# Controller_Board_Main.net
KiCad netlist of a schematic drawn in Altium Designer
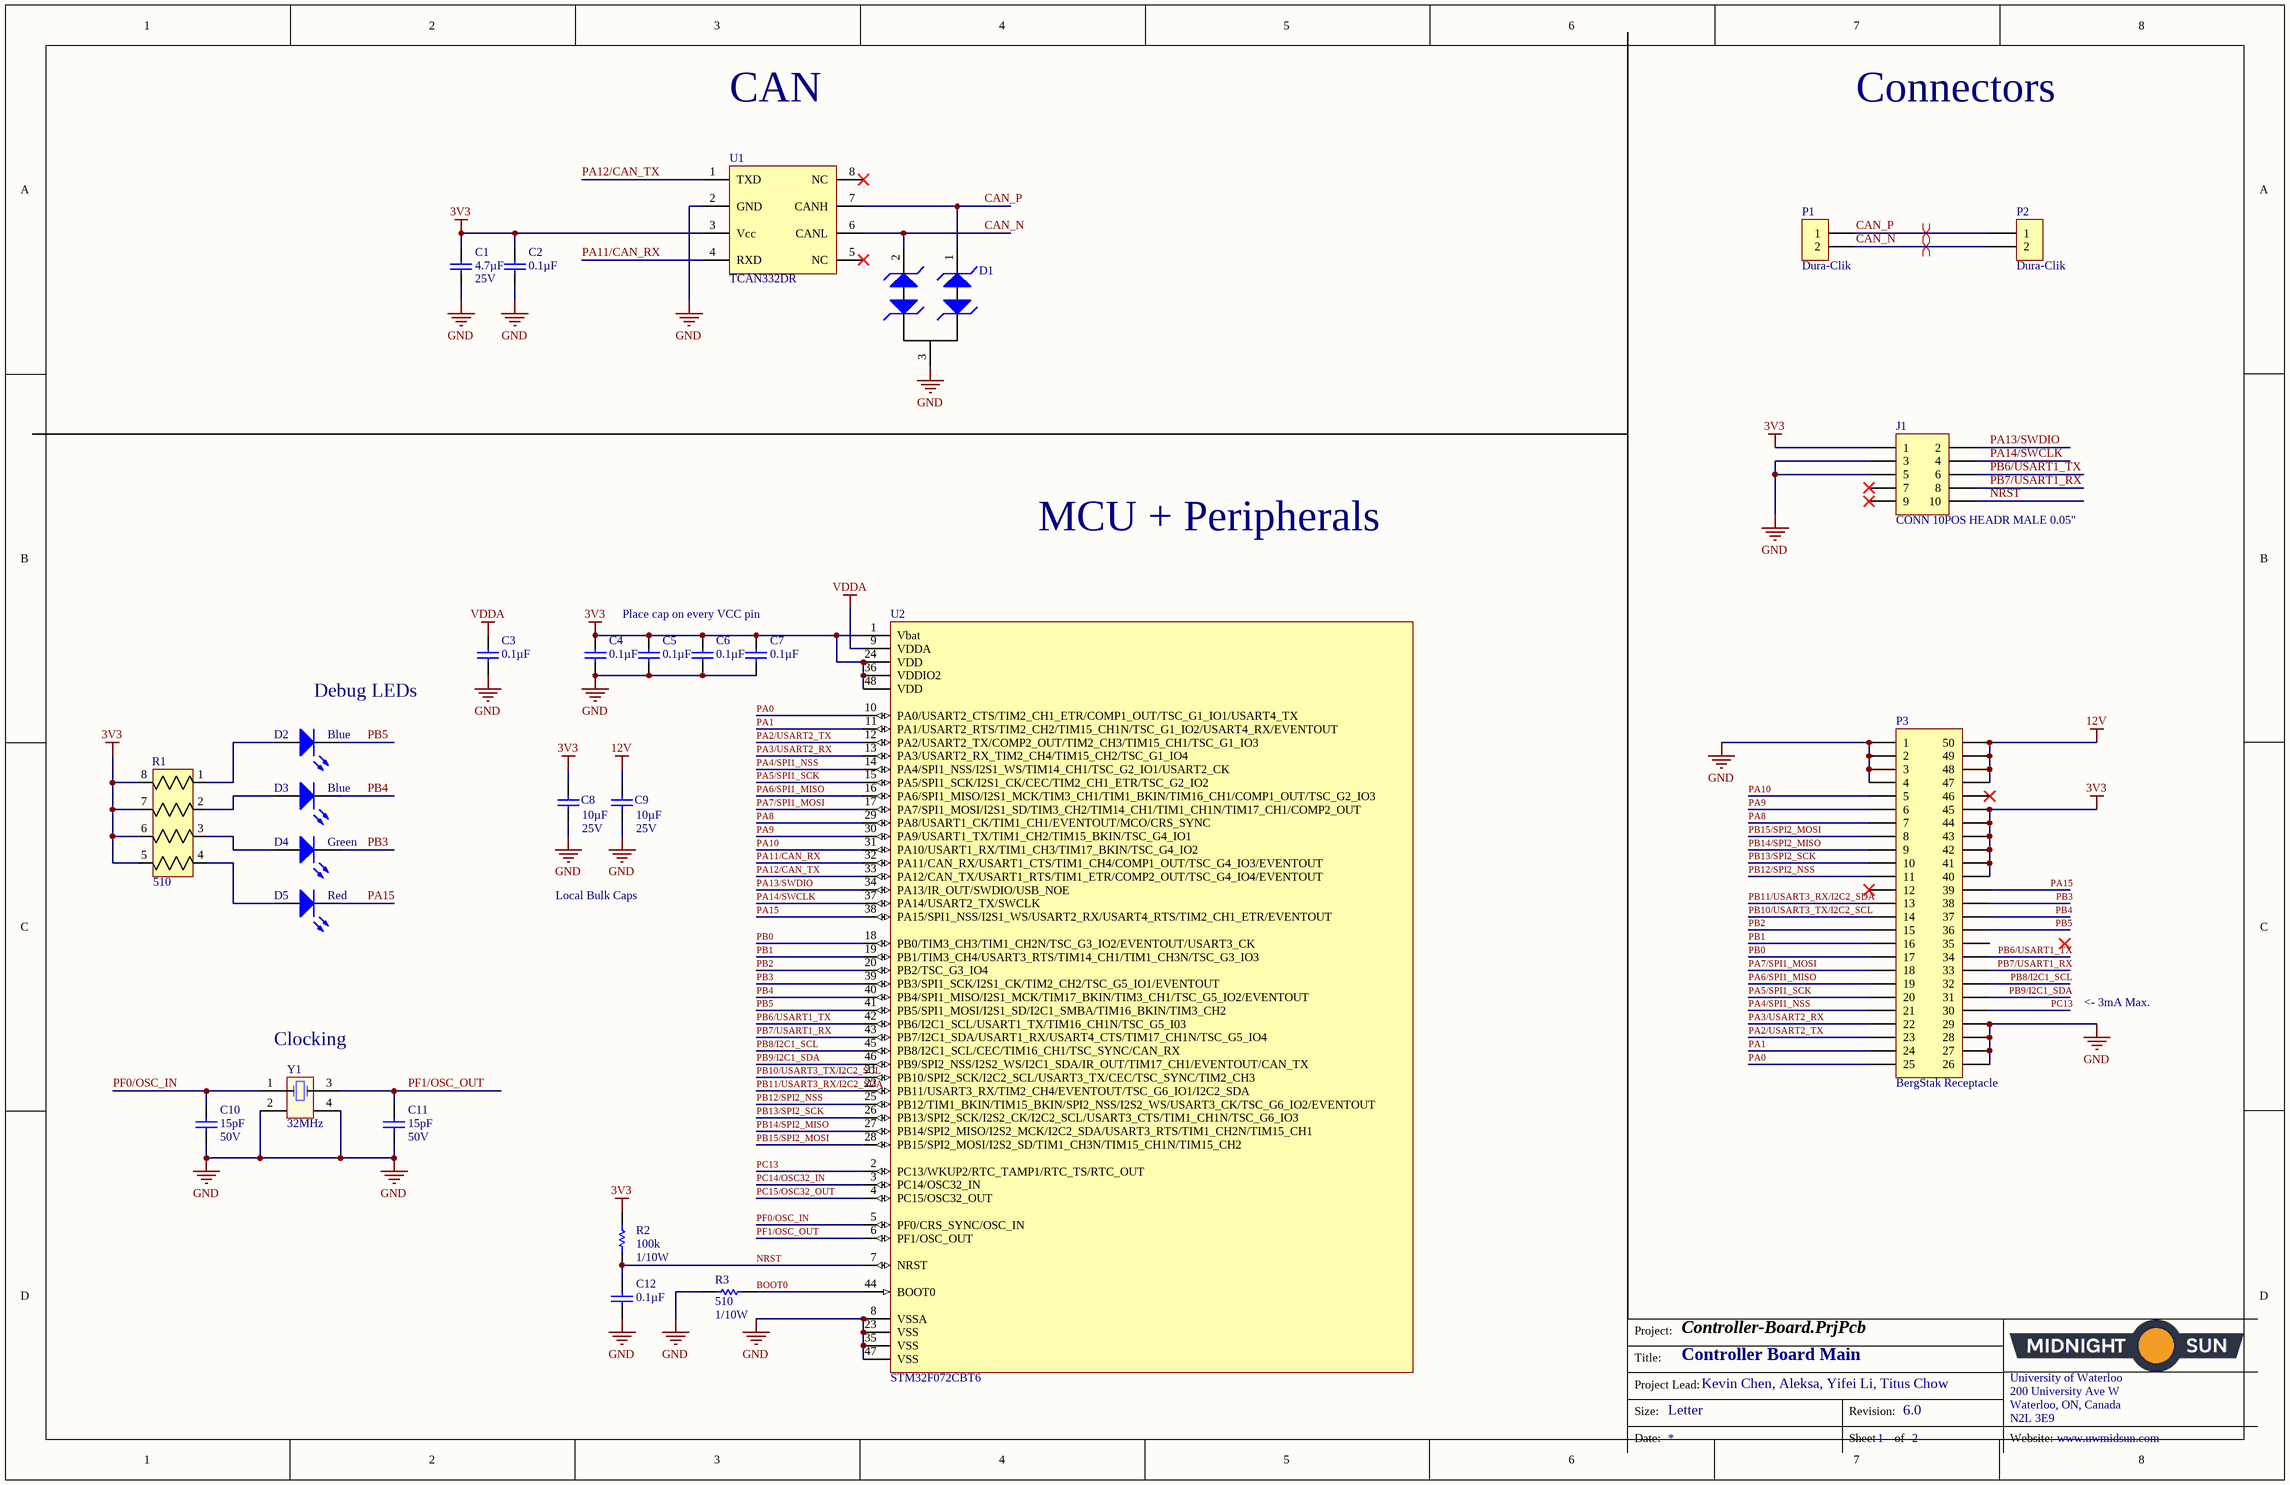
[diagram p0: Controller_Board_Main.SchDoc]

(export (version "E")
  (design (tool "Eeschema 10.0.6"))
  (components
    (comp (ref "C1")
      (value "CAP CER 4.7UF 25V 10% X5R 0603")
      (footprint "CAP, 0603")
      (description "4.7µF ±10% 25V Ceramic Capacitor X5R 0603 (1608 Metric)")
      (fields
        (field (name "VOLTAGE") "25V")
        (field (name "TOLERANCE") "±10%")
        (field (name "CAPACITANCE") "4.7µF")
      )
      (libsource (lib "Schematic Diagrams") (part "CAP CER 4.7UF 25V 10% X5R 0603"))
    )
    (comp (ref "C2")
      (value "CAP CER 0.1UF 50V 10% X7R 0603")
      (footprint "CAP, 0603")
      (description "0.10µF ±10% 50V Ceramic Capacitor X7R 0603 (1608 Metric)")
      (fields
        (field (name "VOLTAGE") "50V")
        (field (name "TOLERANCE") "±10%")
        (field (name "CAPACITANCE") "0.1µF")
      )
      (libsource (lib "Schematic Diagrams") (part "CAP CER 0.1UF 50V 10% X7R 0603"))
    )
    (comp (ref "C3")
      (value "CAP CER 0.1UF 50V 10% X7R 0603")
      (footprint "CAP, 0603")
      (description "0.10µF ±10% 50V Ceramic Capacitor X7R 0603 (1608 Metric)")
      (fields
        (field (name "VOLTAGE") "50V")
        (field (name "TOLERANCE") "±10%")
        (field (name "CAPACITANCE") "0.1µF")
      )
      (libsource (lib "Schematic Diagrams") (part "CAP CER 0.1UF 50V 10% X7R 0603"))
    )
    (comp (ref "C4")
      (value "CAP CER 0.1UF 50V 10% X7R 0603")
      (footprint "CAP, 0603")
      (description "0.10µF ±10% 50V Ceramic Capacitor X7R 0603 (1608 Metric)")
      (fields
        (field (name "VOLTAGE") "50V")
        (field (name "TOLERANCE") "±10%")
        (field (name "CAPACITANCE") "0.1µF")
      )
      (libsource (lib "Schematic Diagrams") (part "CAP CER 0.1UF 50V 10% X7R 0603"))
    )
    (comp (ref "C5")
      (value "CAP CER 0.1UF 50V 10% X7R 0603")
      (footprint "CAP, 0603")
      (description "0.10µF ±10% 50V Ceramic Capacitor X7R 0603 (1608 Metric)")
      (fields
        (field (name "VOLTAGE") "50V")
        (field (name "TOLERANCE") "±10%")
        (field (name "CAPACITANCE") "0.1µF")
      )
      (libsource (lib "Schematic Diagrams") (part "CAP CER 0.1UF 50V 10% X7R 0603"))
    )
    (comp (ref "C6")
      (value "CAP CER 0.1UF 50V 10% X7R 0603")
      (footprint "CAP, 0603")
      (description "0.10µF ±10% 50V Ceramic Capacitor X7R 0603 (1608 Metric)")
      (fields
        (field (name "VOLTAGE") "50V")
        (field (name "TOLERANCE") "±10%")
        (field (name "CAPACITANCE") "0.1µF")
      )
      (libsource (lib "Schematic Diagrams") (part "CAP CER 0.1UF 50V 10% X7R 0603"))
    )
    (comp (ref "C7")
      (value "CAP CER 0.1UF 50V 10% X7R 0603")
      (footprint "CAP, 0603")
      (description "0.10µF ±10% 50V Ceramic Capacitor X7R 0603 (1608 Metric)")
      (fields
        (field (name "VOLTAGE") "50V")
        (field (name "TOLERANCE") "±10%")
        (field (name "CAPACITANCE") "0.1µF")
      )
      (libsource (lib "Schematic Diagrams") (part "CAP CER 0.1UF 50V 10% X7R 0603"))
    )
    (comp (ref "C8")
      (value "CAP CER 10uF 25V 10% X5R 0805")
      (footprint "CAP, 0805")
      (description "10µF ±10% 25V Ceramic Capacitor X5R 0805 (2012 Metric)")
      (fields
        (field (name "MANUFACTURER") "Murata Electronics North America")
        (field (name "MANUFACTURER PART NUMBER") "GRM21BR61E106KA73L")
        (field (name "VOLTAGE - RATED") "25V")
        (field (name "CAPACITANCE") "10µF")
      )
      (libsource (lib "Schematic Diagrams") (part "CAP CER 10uF 25V 10% X5R 0805"))
    )
    (comp (ref "C9")
      (value "CAP CER 10uF 25V 10% X5R 0805")
      (footprint "CAP, 0805")
      (description "10µF ±10% 25V Ceramic Capacitor X5R 0805 (2012 Metric)")
      (fields
        (field (name "MANUFACTURER") "Murata Electronics North America")
        (field (name "MANUFACTURER PART NUMBER") "GRM21BR61E106KA73L")
        (field (name "VOLTAGE - RATED") "25V")
        (field (name "CAPACITANCE") "10µF")
      )
      (libsource (lib "Schematic Diagrams") (part "CAP CER 10uF 25V 10% X5R 0805"))
    )
    (comp (ref "C10")
      (value "CAP CER 15PF 50V ±5% NPO 0603")
      (footprint "CAP, 0603")
      (description "15pF ±5% 50V Ceramic Capacitor C0G, NP0 0603 (1608 Metric)")
      (fields
        (field (name "VOLTAGE") "50V")
        (field (name "TOLERANCE") "±5%")
        (field (name "CAPACITANCE") "15pF")
      )
      (libsource (lib "Schematic Diagrams") (part "CAP CER 15PF 50V ±5% NPO 0603"))
    )
    (comp (ref "C11")
      (value "CAP CER 15PF 50V ±5% NPO 0603")
      (footprint "CAP, 0603")
      (description "15pF ±5% 50V Ceramic Capacitor C0G, NP0 0603 (1608 Metric)")
      (fields
        (field (name "VOLTAGE") "50V")
        (field (name "TOLERANCE") "±5%")
        (field (name "CAPACITANCE") "15pF")
      )
      (libsource (lib "Schematic Diagrams") (part "CAP CER 15PF 50V ±5% NPO 0603"))
    )
    (comp (ref "C12")
      (value "CAP CER 0.1UF 50V 10% X7R 0603")
      (footprint "CAP, 0603")
      (description "0.10µF ±10% 50V Ceramic Capacitor X7R 0603 (1608 Metric)")
      (fields
        (field (name "VOLTAGE") "50V")
        (field (name "TOLERANCE") "±10%")
        (field (name "CAPACITANCE") "0.1µF")
      )
      (libsource (lib "Schematic Diagrams") (part "CAP CER 0.1UF 50V 10% X7R 0603"))
    )
    (comp (ref "D1")
      (value "DIODE TVS 24VWM 70VC SOT23")
      (footprint "SOT23")
      (description "TVS DIODE 24VWM 70VC SOT23")
      (libsource (lib "Schematic Diagrams") (part "DIODE TVS 24VWM 70VC SOT23"))
    )
    (comp (ref "D2")
      (value "LED BLUE CLEAR 2.8V 0603")
      (footprint "DIOC1608X06N")
      (description "Blue 470nm LED Indication - Discrete 2.8V 0603 (1608 Metric)")
      (fields (field (name "COLOR") "Blue"))
      (libsource (lib "Schematic Diagrams") (part "LED BLUE CLEAR 2.8V 0603"))
    )
    (comp (ref "D3")
      (value "LED BLUE CLEAR 2.8V 0603")
      (footprint "DIOC1608X06N")
      (description "Blue 470nm LED Indication - Discrete 2.8V 0603 (1608 Metric)")
      (fields (field (name "COLOR") "Blue"))
      (libsource (lib "Schematic Diagrams") (part "LED BLUE CLEAR 2.8V 0603"))
    )
    (comp (ref "D4")
      (value "LED GREEN CLEAR 2V 0603")
      (footprint "LED_0603")
      (description "Green 572nm LED Indication - Discrete 2V 0603 (1608 Metric)")
      (fields
        (field (name "COLOR") "Green")
        (field (name "MANUFACTURER") "Wurth Electronics Inc.")
        (field (name "MANUFACTURER PART NUMBER") "150060VS75000")
      )
      (libsource (lib "Schematic Diagrams") (part "LED GREEN CLEAR 2V 0603"))
    )
    (comp (ref "D5")
      (value "LED RED CLEAR 2V 0603")
      (footprint "LED_0603")
      (description "Red 631nm LED Indication - Discrete 2V 0603 (1608 Metric)")
      (fields
        (field (name "COLOR") "Red")
        (field (name "MANUFACTURER") "Wurth Electronics Inc.")
        (field (name "MANUFACTURER PART NUMBER") "150060RS75000")
      )
      (libsource (lib "Schematic Diagrams") (part "LED RED CLEAR 2V 0603"))
    )
    (comp (ref "J1")
      (value "CONN 10POS HEADR MALE 0.05\"")
      (footprint "CONN, 10POS 0.05\" Debug Header")
      (description "10 Positions Header Connector 0.050\" (1.27mm) Surface Mount Gold")
      (libsource (lib "Schematic Diagrams") (part "CONN 10POS HEADR MALE 0.05{dblquote}"))
    )
    (comp (ref "P1")
      (value "Dura-Clik")
      (footprint "CONN, 2POS Dura-Click Vertical")
      (description "2 Positions Header, Shrouded Connector 0.079\" (2.00mm) Surface Mount, Vertical Tin")
      (fields
        (field (name "MANUFACTURER") "Molex, LLC")
        (field (name "MANUFACTURER PART NUMBER") "5600200220")
      )
      (libsource (lib "Schematic Diagrams") (part "CONN 2POS DURA-CLIK 0.079{dblquote} VERT"))
    )
    (comp (ref "P2")
      (value "Dura-Clik")
      (footprint "CONN, 2POS Dura-Click Vertical")
      (description "2 Positions Header, Shrouded Connector 0.079\" (2.00mm) Surface Mount, Vertical Tin")
      (fields
        (field (name "MANUFACTURER") "Molex, LLC")
        (field (name "MANUFACTURER PART NUMBER") "5600200220")
      )
      (libsource (lib "") (part "CONN 2POS DURA-CLIK 0.079{dblquote} VERT_1"))
    )
    (comp (ref "P3")
      (value "CONN 50POS Bergstak Receptacle 0.02\"")
      (footprint "CONN, Bergstak 50 Pos Receptacle")
      (description "50 Position Connector Receptacle, Center Strip Contacts Surface Mount Gold")
      (fields (field (name "SERIES") "BergStak Receptacle"))
      (libsource (lib "Schematic Diagrams") (part "CONN 50POS Bergstak Receptacle 0.02{dblquote}"))
    )
    (comp (ref "R1")
      (value "RES ARRAY 510 OHM 5% 4RES")
      (footprint "RES ARRAY 4 POS 0804")
      (description "RES ARRAY SMD 510 OHM 5% 4RES EXB-N8V511JX")
      (fields
        (field (name "MANUFACTURER") "Panasonic Electronic Components")
        (field (name "MANUFACTURER PART NUMBER") "EXB-N8V511JX")
        (field (name "RESISTANCE (OHMS)") "510")
      )
      (libsource (lib "Schematic Diagrams") (part "RES ARRAY 510 OHM 5% 4RES EXB-N8V511JX"))
    )
    (comp (ref "R2")
      (value "RES 100K OHM 5% 1/8W 0603")
      (footprint "RES, 0603")
      (description "RES SMD 100K OHM 5% 1/10W 0603")
      (fields
        (field (name "TOLERANCE") "±5%")
        (field (name "RESISTANCE") "100k")
        (field (name "POWER") "1/10W")
      )
      (libsource (lib "Schematic Diagrams") (part "RES 100K OHM 5% 1/8W 0603"))
    )
    (comp (ref "R3")
      (value "RES 510 OHM 5% 1/10W 0603")
      (footprint "RES, 0603")
      (description "RES SMD 510 OHM 5% 1/10W 0603")
      (fields
        (field (name "TOLERANCE") "±5%")
        (field (name "RESISTANCE") "510")
        (field (name "POWER") "1/10W")
      )
      (libsource (lib "Schematic Diagrams") (part "RES 510 OHM 5% 1/10W 0603"))
    )
    (comp (ref "U1")
      (value "IC CAN Tranceiver TCAN332DR")
      (footprint "TSOP65P280X145-8N")
      (description "1/1 Transceiver CAN 8-SOIC")
      (fields
        (field (name "MANUFACTURER PART NUMBER") "TCAN332DR")
        (field (name "DIGIKEY PART NUMBER") "296-43711-1-ND")
      )
      (libsource (lib "Schematic Diagrams") (part "IC CAN Tranceiver TCAN332DR"))
    )
    (comp (ref "U2")
      (value "IC MCU 32BIT 128KB FLASH 48LQFP")
      (footprint "TSQFP50P890X890X160-48M")
      (description "ARM® Cortex®-M0 STM32 F0 Microcontroller IC 32-Bit 48MHz 128KB (128K x 8) FLASH 48-LQFP (7x7)")
      (fields (field (name "MANUFACTURER PART NUMBER 1") "STM32F072CBT6"))
      (libsource (lib "Schematic Diagrams") (part "IC MCU 32BIT 128KB FLASH 48LQFP"))
    )
    (comp (ref "Y1")
      (value "CRYSTAL 32 MHz 8pF 4-SMD")
      (footprint "CX2520DB CRYSTAL")
      (description "32MHz ±15ppm Crystal 8pF 50 Ohm -40°C ~ 85°C AEC-Q200 Surface Mount 4-SMD, No Lead")
      (fields (field (name "FREQUENCY") "32MHz"))
      (libsource (lib "Schematic Diagrams") (part "CRYSTAL 32 MHz 8pF 4-SMD"))
    )
  )
  (nets
    (net (code "1") (name "/BOOT0") (class "Default")
      (node (ref "R3") (pin "2") (pinfunction "2_2") (pintype "passive"))
      (node (ref "U2") (pin "44") (pinfunction "BOOT0_44") (pintype "input"))
    )
    (net (code "2") (name "/CAN_N") (class "Default")
      (node (ref "D1") (pin "2") (pinfunction "Cathode2_2") (pintype "passive"))
      (node (ref "P1") (pin "2") (pinfunction "2_2") (pintype "passive"))
      (node (ref "P2") (pin "2") (pinfunction "2_2") (pintype "passive"))
      (node (ref "U1") (pin "6") (pinfunction "CANL_6") (pintype "passive"))
    )
    (net (code "3") (name "/CAN_P") (class "Default")
      (node (ref "D1") (pin "1") (pinfunction "Cathode1_1") (pintype "passive"))
      (node (ref "P1") (pin "1") (pinfunction "1_1") (pintype "passive"))
      (node (ref "P2") (pin "1") (pinfunction "1_1") (pintype "passive"))
      (node (ref "U1") (pin "7") (pinfunction "CANH_7") (pintype "passive"))
    )
    (net (code "4") (name "/NRST") (class "Default")
      (node (ref "C12") (pin "2") (pinfunction "2_2") (pintype "passive"))
      (node (ref "J1") (pin "10") (pinfunction "10_10") (pintype "passive"))
      (node (ref "R2") (pin "1") (pinfunction "1_1") (pintype "passive"))
      (node (ref "U2") (pin "7") (pinfunction "NRST_7") (pintype "bidirectional"))
    )
    (net (code "5") (name "/PA0") (class "Default")
      (node (ref "P3") (pin "25") (pinfunction "25_25") (pintype "passive"))
      (node (ref "U2") (pin "10") (pinfunction "PA0/USART2_CTS/TIM2_CH1_ETR/COMP1_OUT/TSC_G1_IO1/USART4_TX_10") (pintype "bidirectional"))
    )
    (net (code "6") (name "/PA1") (class "Default")
      (node (ref "P3") (pin "24") (pinfunction "24_24") (pintype "passive"))
      (node (ref "U2") (pin "11") (pinfunction "PA1/USART2_RTS/TIM2_CH2/TIM15_CH1N/TSC_G1_IO2/USART4_RX/EVENTOUT_11") (pintype "bidirectional"))
    )
    (net (code "7") (name "/PA2{slash}USART2_TX") (class "Default")
      (node (ref "P3") (pin "23") (pinfunction "23_23") (pintype "passive"))
      (node (ref "U2") (pin "12") (pinfunction "PA2/USART2_TX/COMP2_OUT/TIM2_CH3/TIM15_CH1/TSC_G1_IO3_12") (pintype "bidirectional"))
    )
    (net (code "8") (name "/PA3{slash}USART2_RX") (class "Default")
      (node (ref "P3") (pin "22") (pinfunction "22_22") (pintype "passive"))
      (node (ref "U2") (pin "13") (pinfunction "PA3/USART2_RX_TIM2_CH4/TIM15_CH2/TSC_G1_IO4_13") (pintype "bidirectional"))
    )
    (net (code "9") (name "/PA4{slash}SPI1_NSS") (class "Default")
      (node (ref "P3") (pin "21") (pinfunction "21_21") (pintype "passive"))
      (node (ref "U2") (pin "14") (pinfunction "PA4/SPI1_NSS/I2S1_WS/TIM14_CH1/TSC_G2_IO1/USART2_CK_14") (pintype "bidirectional"))
    )
    (net (code "10") (name "/PA5{slash}SPI1_SCK") (class "Default")
      (node (ref "P3") (pin "20") (pinfunction "20_20") (pintype "passive"))
      (node (ref "U2") (pin "15") (pinfunction "PA5/SPI1_SCK/I2S1_CK/CEC/TIM2_CH1_ETR/TSC_G2_IO2_15") (pintype "bidirectional"))
    )
    (net (code "11") (name "/PA6{slash}SPI1_MISO") (class "Default")
      (node (ref "P3") (pin "19") (pinfunction "19_19") (pintype "passive"))
      (node (ref "U2") (pin "16") (pinfunction "PA6/SPI1_MISO/I2S1_MCK/TIM3_CH1/TIM1_BKIN/TIM16_CH1/COMP1_OUT/TSC_G2_IO3_16") (pintype "bidirectional"))
    )
    (net (code "12") (name "/PA7{slash}SPI1_MOSI") (class "Default")
      (node (ref "P3") (pin "18") (pinfunction "18_18") (pintype "passive"))
      (node (ref "U2") (pin "17") (pinfunction "PA7/SPI1_MOSI/I2S1_SD/TIM3_CH2/TIM14_CH1/TIM1_CH1N/TIM17_CH1/COMP2_OUT_17") (pintype "bidirectional"))
    )
    (net (code "13") (name "/PA8") (class "Default")
      (node (ref "P3") (pin "7") (pinfunction "7_7") (pintype "passive"))
      (node (ref "U2") (pin "29") (pinfunction "PA8/USART1_CK/TIM1_CH1/EVENTOUT/MCO/CRS_SYNC_29") (pintype "bidirectional"))
    )
    (net (code "14") (name "/PA9") (class "Default")
      (node (ref "P3") (pin "6") (pinfunction "6_6") (pintype "passive"))
      (node (ref "U2") (pin "30") (pinfunction "PA9/USART1_TX/TIM1_CH2/TIM15_BKIN/TSC_G4_IO1_30") (pintype "bidirectional"))
    )
    (net (code "15") (name "/PA10") (class "Default")
      (node (ref "P3") (pin "5") (pinfunction "5_5") (pintype "passive"))
      (node (ref "U2") (pin "31") (pinfunction "PA10/USART1_RX/TIM1_CH3/TIM17_BKIN/TSC_G4_IO2_31") (pintype "bidirectional"))
    )
    (net (code "16") (name "/PA11{slash}CAN_RX") (class "Default")
      (node (ref "U1") (pin "4") (pinfunction "RXD_4") (pintype "passive"))
      (node (ref "U2") (pin "32") (pinfunction "PA11/CAN_RX/USART1_CTS/TIM1_CH4/COMP1_OUT/TSC_G4_IO3/EVENTOUT_32") (pintype "bidirectional"))
    )
    (net (code "17") (name "/PA12{slash}CAN_TX") (class "Default")
      (node (ref "U1") (pin "1") (pinfunction "TXD_1") (pintype "passive"))
      (node (ref "U2") (pin "33") (pinfunction "PA12/CAN_TX/USART1_RTS/TIM1_ETR/COMP2_OUT/TSC_G4_IO4/EVENTOUT_33") (pintype "bidirectional"))
    )
    (net (code "18") (name "/PA13{slash}SWDIO") (class "Default")
      (node (ref "J1") (pin "2") (pinfunction "2_2") (pintype "passive"))
      (node (ref "U2") (pin "34") (pinfunction "PA13/IR_OUT/SWDIO/USB_NOE_34") (pintype "bidirectional"))
    )
    (net (code "19") (name "/PA14{slash}SWCLK") (class "Default")
      (node (ref "J1") (pin "4") (pinfunction "4_4") (pintype "passive"))
      (node (ref "U2") (pin "37") (pinfunction "PA14/USART2_TX/SWCLK_37") (pintype "bidirectional"))
    )
    (net (code "20") (name "/PA15") (class "Default")
      (node (ref "D5") (pin "2") (pinfunction "K_2") (pintype "passive"))
      (node (ref "P3") (pin "39") (pinfunction "39_39") (pintype "passive"))
      (node (ref "U2") (pin "38") (pinfunction "PA15/SPI1_NSS/I2S1_WS/USART2_RX/USART4_RTS/TIM2_CH1_ETR/EVENTOUT_38") (pintype "bidirectional"))
    )
    (net (code "21") (name "/PB0") (class "Default")
      (node (ref "P3") (pin "17") (pinfunction "17_17") (pintype "passive"))
      (node (ref "U2") (pin "18") (pinfunction "PB0/TIM3_CH3/TIM1_CH2N/TSC_G3_IO2/EVENTOUT/USART3_CK_18") (pintype "bidirectional"))
    )
    (net (code "22") (name "/PB1") (class "Default")
      (node (ref "P3") (pin "16") (pinfunction "16_16") (pintype "passive"))
      (node (ref "U2") (pin "19") (pinfunction "PB1/TIM3_CH4/USART3_RTS/TIM14_CH1/TIM1_CH3N/TSC_G3_IO3_19") (pintype "bidirectional"))
    )
    (net (code "23") (name "/PB2") (class "Default")
      (node (ref "P3") (pin "15") (pinfunction "15_15") (pintype "passive"))
      (node (ref "U2") (pin "20") (pinfunction "PB2/TSC_G3_IO4_20") (pintype "bidirectional"))
    )
    (net (code "24") (name "/PB3") (class "Default")
      (node (ref "D4") (pin "2") (pinfunction "K_2") (pintype "passive"))
      (node (ref "P3") (pin "38") (pinfunction "38_38") (pintype "passive"))
      (node (ref "U2") (pin "39") (pinfunction "PB3/SPI1_SCK/I2S1_CK/TIM2_CH2/TSC_G5_IO1/EVENTOUT_39") (pintype "bidirectional"))
    )
    (net (code "25") (name "/PB4") (class "Default")
      (node (ref "D3") (pin "2") (pinfunction "K_2") (pintype "passive"))
      (node (ref "P3") (pin "37") (pinfunction "37_37") (pintype "passive"))
      (node (ref "U2") (pin "40") (pinfunction "PB4/SPI1_MISO/I2S1_MCK/TIM17_BKIN/TIM3_CH1/TSC_G5_IO2/EVENTOUT_40") (pintype "bidirectional"))
    )
    (net (code "26") (name "/PB5") (class "Default")
      (node (ref "D2") (pin "2") (pinfunction "K_2") (pintype "passive"))
      (node (ref "P3") (pin "36") (pinfunction "36_36") (pintype "passive"))
      (node (ref "U2") (pin "41") (pinfunction "PB5/SPI1_MOSI/I2S1_SD/I2C1_SMBA/TIM16_BKIN/TIM3_CH2_41") (pintype "bidirectional"))
    )
    (net (code "27") (name "/PB6{slash}USART1_TX") (class "Default")
      (node (ref "J1") (pin "6") (pinfunction "6_6") (pintype "passive"))
      (node (ref "P3") (pin "34") (pinfunction "34_34") (pintype "passive"))
      (node (ref "U2") (pin "42") (pinfunction "PB6/I2C1_SCL/USART1_TX/TIM16_CH1N/TSC_G5_I03_42") (pintype "bidirectional"))
    )
    (net (code "28") (name "/PB7{slash}USART1_RX") (class "Default")
      (node (ref "J1") (pin "8") (pinfunction "8_8") (pintype "passive"))
      (node (ref "P3") (pin "33") (pinfunction "33_33") (pintype "passive"))
      (node (ref "U2") (pin "43") (pinfunction "PB7/I2C1_SDA/USART1_RX/USART4_CTS/TIM17_CH1N/TSC_G5_IO4_43") (pintype "bidirectional"))
    )
    (net (code "29") (name "/PB8{slash}I2C1_SCL") (class "Default")
      (node (ref "P3") (pin "32") (pinfunction "32_32") (pintype "passive"))
      (node (ref "U2") (pin "45") (pinfunction "PB8/I2C1_SCL/CEC/TIM16_CH1/TSC_SYNC/CAN_RX_45") (pintype "bidirectional"))
    )
    (net (code "30") (name "/PB9{slash}I2C1_SDA") (class "Default")
      (node (ref "P3") (pin "31") (pinfunction "31_31") (pintype "passive"))
      (node (ref "U2") (pin "46") (pinfunction "PB9/SPI2_NSS/I2S2_WS/I2C1_SDA/IR_OUT/TIM17_CH1/EVENTOUT/CAN_TX_46") (pintype "bidirectional"))
    )
    (net (code "31") (name "/PB10{slash}USART3_TX{slash}I2C2_SCL") (class "Default")
      (node (ref "P3") (pin "14") (pinfunction "14_14") (pintype "passive"))
      (node (ref "U2") (pin "21") (pinfunction "PB10/SPI2_SCK/I2C2_SCL/USART3_TX/CEC/TSC_SYNC/TIM2_CH3_21") (pintype "bidirectional"))
    )
    (net (code "32") (name "/PB11{slash}USART3_RX{slash}I2C2_SDA") (class "Default")
      (node (ref "P3") (pin "13") (pinfunction "13_13") (pintype "passive"))
      (node (ref "U2") (pin "22") (pinfunction "PB11/USART3_RX/TIM2_CH4/EVENTOUT/TSC_G6_IO1/I2C2_SDA_22") (pintype "bidirectional"))
    )
    (net (code "33") (name "/PB12{slash}SPI2_NSS") (class "Default")
      (node (ref "P3") (pin "11") (pinfunction "11_11") (pintype "passive"))
      (node (ref "U2") (pin "25") (pinfunction "PB12/TIM1_BKIN/TIM15_BKIN/SPI2_NSS/I2S2_WS/USART3_CK/TSC_G6_IO2/EVENTOUT_25") (pintype "bidirectional"))
    )
    (net (code "34") (name "/PB13{slash}SPI2_SCK") (class "Default")
      (node (ref "P3") (pin "10") (pinfunction "10_10") (pintype "passive"))
      (node (ref "U2") (pin "26") (pinfunction "PB13/SPI2_SCK/I2S2_CK/I2C2_SCL/USART3_CTS/TIM1_CH1N/TSC_G6_IO3_26") (pintype "bidirectional"))
    )
    (net (code "35") (name "/PB14{slash}SPI2_MISO") (class "Default")
      (node (ref "P3") (pin "9") (pinfunction "9_9") (pintype "passive"))
      (node (ref "U2") (pin "27") (pinfunction "PB14/SPI2_MISO/I2S2_MCK/I2C2_SDA/USART3_RTS/TIM1_CH2N/TIM15_CH1_27") (pintype "bidirectional"))
    )
    (net (code "36") (name "/PB15{slash}SPI2_MOSI") (class "Default")
      (node (ref "P3") (pin "8") (pinfunction "8_8") (pintype "passive"))
      (node (ref "U2") (pin "28") (pinfunction "PB15/SPI2_MOSI/I2S2_SD/TIM1_CH3N/TIM15_CH1N/TIM15_CH2_28") (pintype "bidirectional"))
    )
    (net (code "37") (name "/PC13") (class "Default")
      (node (ref "P3") (pin "30") (pinfunction "30_30") (pintype "passive"))
      (node (ref "U2") (pin "2") (pinfunction "PC13/WKUP2/RTC_TAMP1/RTC_TS/RTC_OUT_2") (pintype "bidirectional"))
    )
    (net (code "38") (name "/PC14{slash}OSC32_IN") (class "Default")
      (node (ref "U2") (pin "3") (pinfunction "PC14/OSC32_IN_3") (pintype "bidirectional"))
    )
    (net (code "39") (name "/PC15{slash}OSC32_OUT") (class "Default")
      (node (ref "U2") (pin "4") (pinfunction "PC15/OSC32_OUT_4") (pintype "bidirectional"))
    )
    (net (code "40") (name "/PF0{slash}OSC_IN") (class "Default")
      (node (ref "C10") (pin "2") (pinfunction "2_2") (pintype "passive"))
      (node (ref "U2") (pin "5") (pinfunction "PF0/CRS_SYNC/OSC_IN_5") (pintype "bidirectional"))
      (node (ref "Y1") (pin "1") (pinfunction "OSC1_1") (pintype "passive"))
    )
    (net (code "41") (name "/PF1{slash}OSC_OUT") (class "Default")
      (node (ref "C11") (pin "2") (pinfunction "2_2") (pintype "passive"))
      (node (ref "U2") (pin "6") (pinfunction "PF1/OSC_OUT_6") (pintype "bidirectional"))
      (node (ref "Y1") (pin "3") (pinfunction "OSC2_3") (pintype "passive"))
    )
    (net (code "42") (name "3V3") (class "Default")
      (node (ref "C1") (pin "2") (pinfunction "2_2") (pintype "passive"))
      (node (ref "C2") (pin "2") (pinfunction "2_2") (pintype "passive"))
      (node (ref "C4") (pin "2") (pinfunction "2_2") (pintype "passive"))
      (node (ref "C5") (pin "2") (pinfunction "2_2") (pintype "passive"))
      (node (ref "C6") (pin "2") (pinfunction "2_2") (pintype "passive"))
      (node (ref "C7") (pin "2") (pinfunction "2_2") (pintype "passive"))
      (node (ref "C8") (pin "1") (pinfunction "1_1") (pintype "passive"))
      (node (ref "J1") (pin "1") (pinfunction "1_1") (pintype "passive"))
      (node (ref "P3") (pin "40") (pinfunction "40_40") (pintype "passive"))
      (node (ref "P3") (pin "41") (pinfunction "41_41") (pintype "passive"))
      (node (ref "P3") (pin "42") (pinfunction "42_42") (pintype "passive"))
      (node (ref "P3") (pin "43") (pinfunction "43_43") (pintype "passive"))
      (node (ref "P3") (pin "44") (pinfunction "44_44") (pintype "passive"))
      (node (ref "P3") (pin "45") (pinfunction "45_45") (pintype "passive"))
      (node (ref "R1") (pin "5") (pinfunction "5_5") (pintype "passive"))
      (node (ref "R1") (pin "6") (pinfunction "6_6") (pintype "passive"))
      (node (ref "R1") (pin "7") (pinfunction "7_7") (pintype "passive"))
      (node (ref "R1") (pin "8") (pinfunction "8_8") (pintype "passive"))
      (node (ref "R2") (pin "2") (pinfunction "2_2") (pintype "passive"))
      (node (ref "U1") (pin "3") (pinfunction "Vcc_3") (pintype "passive"))
      (node (ref "U2") (pin "1") (pinfunction "Vbat_1") (pintype "power_in"))
      (node (ref "U2") (pin "24") (pinfunction "VDD_24") (pintype "power_in"))
      (node (ref "U2") (pin "36") (pinfunction "VDDIO2_36") (pintype "power_in"))
      (node (ref "U2") (pin "48") (pinfunction "VDD_48") (pintype "power_in"))
    )
    (net (code "43") (name "12V") (class "Default")
      (node (ref "C9") (pin "1") (pinfunction "1_1") (pintype "passive"))
      (node (ref "P3") (pin "47") (pinfunction "47_47") (pintype "passive"))
      (node (ref "P3") (pin "48") (pinfunction "48_48") (pintype "passive"))
      (node (ref "P3") (pin "49") (pinfunction "49_49") (pintype "passive"))
      (node (ref "P3") (pin "50") (pinfunction "50_50") (pintype "passive"))
    )
    (net (code "44") (name "GND") (class "Default")
      (node (ref "C1") (pin "1") (pinfunction "1_1") (pintype "passive"))
      (node (ref "C10") (pin "1") (pinfunction "1_1") (pintype "passive"))
      (node (ref "C11") (pin "1") (pinfunction "1_1") (pintype "passive"))
      (node (ref "C12") (pin "1") (pinfunction "1_1") (pintype "passive"))
      (node (ref "C2") (pin "1") (pinfunction "1_1") (pintype "passive"))
      (node (ref "C3") (pin "1") (pinfunction "1_1") (pintype "passive"))
      (node (ref "C4") (pin "1") (pinfunction "1_1") (pintype "passive"))
      (node (ref "C5") (pin "1") (pinfunction "1_1") (pintype "passive"))
      (node (ref "C6") (pin "1") (pinfunction "1_1") (pintype "passive"))
      (node (ref "C7") (pin "1") (pinfunction "1_1") (pintype "passive"))
      (node (ref "C8") (pin "2") (pinfunction "2_2") (pintype "passive"))
      (node (ref "C9") (pin "2") (pinfunction "2_2") (pintype "passive"))
      (node (ref "D1") (pin "3") (pinfunction "Common_Cathode_3") (pintype "power_in"))
      (node (ref "J1") (pin "3") (pinfunction "3_3") (pintype "passive"))
      (node (ref "J1") (pin "5") (pinfunction "5_5") (pintype "passive"))
      (node (ref "P3") (pin "1") (pinfunction "1_1") (pintype "passive"))
      (node (ref "P3") (pin "2") (pinfunction "2_2") (pintype "passive"))
      (node (ref "P3") (pin "26") (pinfunction "26_26") (pintype "passive"))
      (node (ref "P3") (pin "27") (pinfunction "27_27") (pintype "passive"))
      (node (ref "P3") (pin "28") (pinfunction "28_28") (pintype "passive"))
      (node (ref "P3") (pin "29") (pinfunction "29_29") (pintype "passive"))
      (node (ref "P3") (pin "3") (pinfunction "3_3") (pintype "passive"))
      (node (ref "P3") (pin "4") (pinfunction "4_4") (pintype "passive"))
      (node (ref "R3") (pin "1") (pinfunction "1_1") (pintype "passive"))
      (node (ref "U1") (pin "2") (pinfunction "GND_2") (pintype "passive"))
      (node (ref "U2") (pin "23") (pinfunction "VSS_23") (pintype "power_in"))
      (node (ref "U2") (pin "35") (pinfunction "VSS_35") (pintype "power_in"))
      (node (ref "U2") (pin "47") (pinfunction "VSS_47") (pintype "power_in"))
      (node (ref "U2") (pin "8") (pinfunction "VSSA_8") (pintype "power_in"))
      (node (ref "Y1") (pin "2") (pinfunction "2_2") (pintype "passive"))
      (node (ref "Y1") (pin "4") (pinfunction "3_4") (pintype "passive"))
    )
    (net (code "45") (name "Net-(D2-A)") (class "Default")
      (node (ref "D2") (pin "1") (pinfunction "A_1") (pintype "passive"))
      (node (ref "R1") (pin "1") (pinfunction "1_1") (pintype "passive"))
    )
    (net (code "46") (name "Net-(D3-A)") (class "Default")
      (node (ref "D3") (pin "1") (pinfunction "A_1") (pintype "passive"))
      (node (ref "R1") (pin "2") (pinfunction "2_2") (pintype "passive"))
    )
    (net (code "47") (name "Net-(D4-A)") (class "Default")
      (node (ref "D4") (pin "1") (pinfunction "A_1") (pintype "passive"))
      (node (ref "R1") (pin "3") (pinfunction "3_3") (pintype "passive"))
    )
    (net (code "48") (name "Net-(D5-A)") (class "Default")
      (node (ref "D5") (pin "1") (pinfunction "A_1") (pintype "passive"))
      (node (ref "R1") (pin "4") (pinfunction "4_4") (pintype "passive"))
    )
    (net (code "49") (name "VDDA") (class "Default")
      (node (ref "C3") (pin "2") (pinfunction "2_2") (pintype "passive"))
      (node (ref "U2") (pin "9") (pinfunction "VDDA_9") (pintype "power_in"))
    )
    (net (code "50") (name "unconnected-(J1-Pad7)") (class "Default")
      (node (ref "J1") (pin "7") (pinfunction "7_7") (pintype "passive+no_connect"))
    )
    (net (code "51") (name "unconnected-(J1-Pad9)") (class "Default")
      (node (ref "J1") (pin "9") (pinfunction "9_9") (pintype "passive+no_connect"))
    )
    (net (code "52") (name "unconnected-(P3-Pad12)") (class "Default")
      (node (ref "P3") (pin "12") (pinfunction "12_12") (pintype "passive+no_connect"))
    )
    (net (code "53") (name "unconnected-(P3-Pad35)") (class "Default")
      (node (ref "P3") (pin "35") (pinfunction "35_35") (pintype "passive"))
    )
    (net (code "54") (name "unconnected-(P3-Pad46)") (class "Default")
      (node (ref "P3") (pin "46") (pinfunction "46_46") (pintype "passive+no_connect"))
    )
    (net (code "55") (name "unconnected-(U1-NC-Pad5)") (class "Default")
      (node (ref "U1") (pin "5") (pinfunction "NC_5") (pintype "passive+no_connect"))
    )
    (net (code "56") (name "unconnected-(U1-NC-Pad8)") (class "Default")
      (node (ref "U1") (pin "8") (pinfunction "NC_8") (pintype "passive+no_connect"))
    )
  )
)
